# ADC.net
KiCad netlist of a schematic drawn in Altium Designer
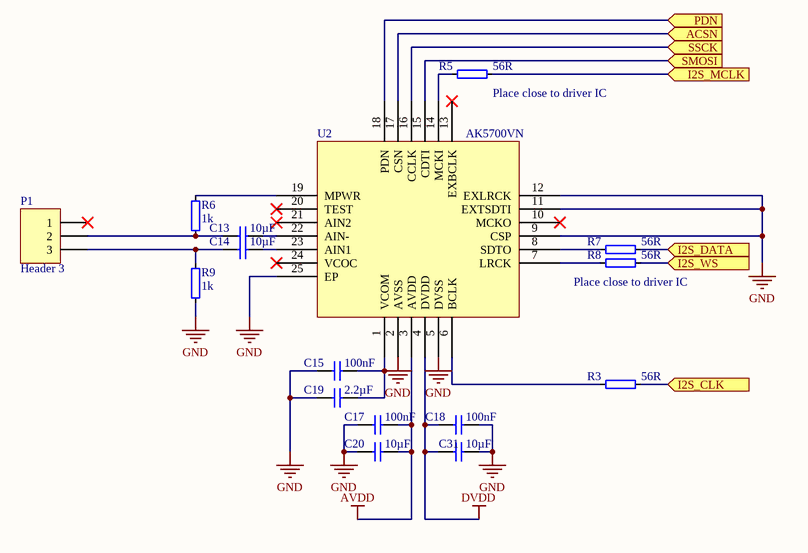
[diagram p0: ADC.SchDoc]

(export (version "E")
  (design (tool "Eeschema 10.0.6"))
  (components
    (comp (ref "C13")
      (value "10µF")
      (footprint "0805")
      (description "Chip Cap 0805")
      (fields (field (name "PART NUMBER") "C0805-10µ") (field (name "PUBLISHER") "Nordic Semiconductor"))
      (libsource (lib "Nordic Passive DB") (part "CAP"))
    )
    (comp (ref "C14")
      (value "10µF")
      (footprint "0805")
      (description "Chip Cap 0805")
      (fields (field (name "PART NUMBER") "C0805-10µ") (field (name "PUBLISHER") "Nordic Semiconductor"))
      (libsource (lib "Nordic Passive DB") (part "CAP"))
    )
    (comp (ref "C15")
      (value "100nF")
      (footprint "0402s")
      (description "Chip Cap 0402")
      (fields (field (name "PART NUMBER") "C0402-100n") (field (name "PUBLISHER") "Nordic Semiconductor"))
      (libsource (lib "Nordic Passive DB") (part "CAP"))
    )
    (comp (ref "C17")
      (value "100nF")
      (footprint "0402s")
      (description "Chip Cap 0402")
      (fields (field (name "PART NUMBER") "C0402-100n") (field (name "PUBLISHER") "Nordic Semiconductor"))
      (libsource (lib "Nordic Passive DB") (part "CAP"))
    )
    (comp (ref "C18")
      (value "100nF")
      (footprint "0402s")
      (description "Chip Cap 0402")
      (fields (field (name "PART NUMBER") "C0402-100n") (field (name "PUBLISHER") "Nordic Semiconductor"))
      (libsource (lib "Nordic Passive DB") (part "CAP"))
    )
    (comp (ref "C19")
      (value "2.2µF")
      (footprint "0603s")
      (description "Chip Cap 0603")
      (fields (field (name "PART NUMBER") "C0603-2µ2") (field (name "PUBLISHER") "Nordic Semiconductor"))
      (libsource (lib "Nordic Passive DB") (part "CAP"))
    )
    (comp (ref "C20")
      (value "10µF")
      (footprint "0603s")
      (description "Chip Cap 0603")
      (fields (field (name "PART NUMBER") "C0603-10µ") (field (name "PUBLISHER") "Nordic Semiconductor"))
      (libsource (lib "Nordic Passive DB") (part "CAP"))
    )
    (comp (ref "C31")
      (value "10µF")
      (footprint "0603s")
      (description "Chip Cap 0603")
      (fields (field (name "PART NUMBER") "C0603-10µ") (field (name "PUBLISHER") "Nordic Semiconductor"))
      (libsource (lib "Nordic Passive DB") (part "CAP"))
    )
    (comp (ref "P1")
      (value "Header 3")
      (footprint "Headphone")
      (description "Header, 3-Pin")
      (fields (field (name "PUBLISHER") "Altium Limited"))
      (libsource (lib "Miscellaneous Connectors") (part "Header 3"))
    )
    (comp (ref "R3")
      (value "56R")
      (footprint "0402s")
      (description "Chip Res 0402")
      (fields (field (name "PART NUMBER") "R0402-56R") (field (name "PUBLISHER") "Nordic Semiconductor"))
      (libsource (lib "Nordic Passive DB") (part "RES_1"))
    )
    (comp (ref "R5")
      (value "56R")
      (footprint "0402s")
      (description "Chip Res 0402")
      (fields (field (name "PART NUMBER") "R0402-56R") (field (name "PUBLISHER") "Nordic Semiconductor"))
      (libsource (lib "Nordic Passive DB") (part "RES_1"))
    )
    (comp (ref "R6")
      (value "1k")
      (footprint "0402s")
      (description "Chip Res 0402")
      (fields (field (name "PART NUMBER") "R0402-1k0") (field (name "PUBLISHER") "Nordic Semiconductor"))
      (libsource (lib "Nordic Passive DB") (part "RES_1"))
    )
    (comp (ref "R7")
      (value "56R")
      (footprint "0402s")
      (description "Chip Res 0402")
      (fields (field (name "PART NUMBER") "R0402-56R") (field (name "PUBLISHER") "Nordic Semiconductor"))
      (libsource (lib "Nordic Passive DB") (part "RES_1"))
    )
    (comp (ref "R8")
      (value "56R")
      (footprint "0402s")
      (description "Chip Res 0402")
      (fields (field (name "PART NUMBER") "R0402-56R") (field (name "PUBLISHER") "Nordic Semiconductor"))
      (libsource (lib "Nordic Passive DB") (part "RES_1"))
    )
    (comp (ref "R9")
      (value "1k")
      (footprint "0402s")
      (description "Chip Res 0402")
      (fields (field (name "PART NUMBER") "R0402-1k0") (field (name "PUBLISHER") "Nordic Semiconductor"))
      (libsource (lib "Nordic Passive DB") (part "RES_1"))
    )
    (comp (ref "U2")
      (value "AK5700VN")
      (footprint "QFN50P400X400X80-24N")
      (libsource (lib "nRF2460") (part "AK5700VN"))
    )
  )
  (nets
    (net (code "1") (name "/ACSN") (class "Default")
      (node (ref "U2") (pin "17") (pinfunction "CSN_17") (pintype "passive"))
    )
    (net (code "2") (name "/I2S_CLK") (class "Default")
      (node (ref "R3") (pin "2") (pinfunction "2_2") (pintype "passive"))
    )
    (net (code "3") (name "/I2S_DATA") (class "Default")
      (node (ref "R7") (pin "2") (pinfunction "2_2") (pintype "passive"))
    )
    (net (code "4") (name "/I2S_MCLK") (class "Default")
      (node (ref "R5") (pin "2") (pinfunction "2_2") (pintype "passive"))
    )
    (net (code "5") (name "/I2S_WS") (class "Default")
      (node (ref "R8") (pin "2") (pinfunction "2_2") (pintype "passive"))
    )
    (net (code "6") (name "/PDN") (class "Default")
      (node (ref "U2") (pin "18") (pinfunction "PDN_18") (pintype "passive"))
    )
    (net (code "7") (name "/SMOSI") (class "Default")
      (node (ref "U2") (pin "15") (pinfunction "CDTI_15") (pintype "passive"))
    )
    (net (code "8") (name "/SSCK") (class "Default")
      (node (ref "U2") (pin "16") (pinfunction "CCLK_16") (pintype "passive"))
    )
    (net (code "9") (name "AVDD") (class "Default")
      (node (ref "C17") (pin "2") (pinfunction "2_2") (pintype "passive"))
      (node (ref "C20") (pin "2") (pinfunction "2_2") (pintype "passive"))
      (node (ref "U2") (pin "3") (pinfunction "AVDD_3") (pintype "power_in"))
    )
    (net (code "10") (name "DVDD") (class "Default")
      (node (ref "C18") (pin "1") (pinfunction "1_1") (pintype "passive"))
      (node (ref "C31") (pin "1") (pinfunction "1_1") (pintype "passive"))
      (node (ref "U2") (pin "4") (pinfunction "DVDD_4") (pintype "power_in"))
    )
    (net (code "11") (name "GND") (class "Default")
      (node (ref "C15") (pin "1") (pinfunction "1_1") (pintype "passive"))
      (node (ref "C17") (pin "1") (pinfunction "1_1") (pintype "passive"))
      (node (ref "C18") (pin "2") (pinfunction "2_2") (pintype "passive"))
      (node (ref "C19") (pin "1") (pinfunction "1_1") (pintype "passive"))
      (node (ref "C20") (pin "1") (pinfunction "1_1") (pintype "passive"))
      (node (ref "C31") (pin "2") (pinfunction "2_2") (pintype "passive"))
      (node (ref "R9") (pin "1") (pinfunction "1_1") (pintype "passive"))
      (node (ref "U2") (pin "11") (pinfunction "EXTSDTI_11") (pintype "passive"))
      (node (ref "U2") (pin "12") (pinfunction "EXLRCK_12") (pintype "passive"))
      (node (ref "U2") (pin "2") (pinfunction "AVSS_2") (pintype "power_in"))
      (node (ref "U2") (pin "25") (pinfunction "EP_25") (pintype "passive"))
      (node (ref "U2") (pin "5") (pinfunction "DVSS_5") (pintype "power_in"))
      (node (ref "U2") (pin "9") (pinfunction "CSP_9") (pintype "passive"))
    )
    (net (code "12") (name "Net-(C13-Pad1)") (class "Default")
      (node (ref "C13") (pin "1") (pinfunction "1_1") (pintype "passive"))
      (node (ref "P1") (pin "2") (pinfunction "2_2") (pintype "passive"))
      (node (ref "R6") (pin "1") (pinfunction "1_1") (pintype "passive"))
    )
    (net (code "13") (name "Net-(C14-Pad1)") (class "Default")
      (node (ref "C14") (pin "1") (pinfunction "1_1") (pintype "passive"))
      (node (ref "P1") (pin "3") (pinfunction "3_3") (pintype "passive"))
      (node (ref "R9") (pin "2") (pinfunction "2_2") (pintype "passive"))
    )
    (net (code "14") (name "Net-(U2-AIN-)") (class "Default")
      (node (ref "C13") (pin "2") (pinfunction "2_2") (pintype "passive"))
      (node (ref "U2") (pin "22") (pinfunction "AIN-_22") (pintype "passive"))
    )
    (net (code "15") (name "Net-(U2-AIN1)") (class "Default")
      (node (ref "C14") (pin "2") (pinfunction "2_2") (pintype "passive"))
      (node (ref "U2") (pin "23") (pinfunction "AIN1_23") (pintype "passive"))
    )
    (net (code "16") (name "Net-(U2-BCLK)") (class "Default")
      (node (ref "R3") (pin "1") (pinfunction "1_1") (pintype "passive"))
      (node (ref "U2") (pin "6") (pinfunction "BCLK_6") (pintype "power_in"))
    )
    (net (code "17") (name "Net-(U2-LRCK)") (class "Default")
      (node (ref "R8") (pin "1") (pinfunction "1_1") (pintype "passive"))
      (node (ref "U2") (pin "7") (pinfunction "LRCK_7") (pintype "power_in"))
    )
    (net (code "18") (name "Net-(U2-MCKI)") (class "Default")
      (node (ref "R5") (pin "1") (pinfunction "1_1") (pintype "passive"))
      (node (ref "U2") (pin "14") (pinfunction "MCKI_14") (pintype "passive"))
    )
    (net (code "19") (name "Net-(U2-MPWR)") (class "Default")
      (node (ref "R6") (pin "2") (pinfunction "2_2") (pintype "passive"))
      (node (ref "U2") (pin "19") (pinfunction "MPWR_19") (pintype "passive"))
    )
    (net (code "20") (name "Net-(U2-SDTO)") (class "Default")
      (node (ref "R7") (pin "1") (pinfunction "1_1") (pintype "passive"))
      (node (ref "U2") (pin "8") (pinfunction "SDTO_8") (pintype "passive"))
    )
    (net (code "21") (name "Net-(U2-VCOM)") (class "Default")
      (node (ref "C15") (pin "2") (pinfunction "2_2") (pintype "passive"))
      (node (ref "C19") (pin "2") (pinfunction "2_2") (pintype "passive"))
      (node (ref "U2") (pin "1") (pinfunction "VCOM_1") (pintype "passive"))
    )
    (net (code "22") (name "unconnected-(P1-Pad1)") (class "Default")
      (node (ref "P1") (pin "1") (pinfunction "1_1") (pintype "passive+no_connect"))
    )
    (net (code "23") (name "unconnected-(U2-AIN2-Pad21)") (class "Default")
      (node (ref "U2") (pin "21") (pinfunction "AIN2_21") (pintype "passive+no_connect"))
    )
    (net (code "24") (name "unconnected-(U2-EXBCLK-Pad13)") (class "Default")
      (node (ref "U2") (pin "13") (pinfunction "EXBCLK_13") (pintype "passive+no_connect"))
    )
    (net (code "25") (name "unconnected-(U2-MCKO-Pad10)") (class "Default")
      (node (ref "U2") (pin "10") (pinfunction "MCKO_10") (pintype "passive+no_connect"))
    )
    (net (code "26") (name "unconnected-(U2-TEST-Pad20)") (class "Default")
      (node (ref "U2") (pin "20") (pinfunction "TEST_20") (pintype "passive+no_connect"))
    )
    (net (code "27") (name "unconnected-(U2-VCOC-Pad24)") (class "Default")
      (node (ref "U2") (pin "24") (pinfunction "VCOC_24") (pintype "passive+no_connect"))
    )
  )
)
